# Schematic.net
KiCad netlist of a schematic drawn in Altium Designer
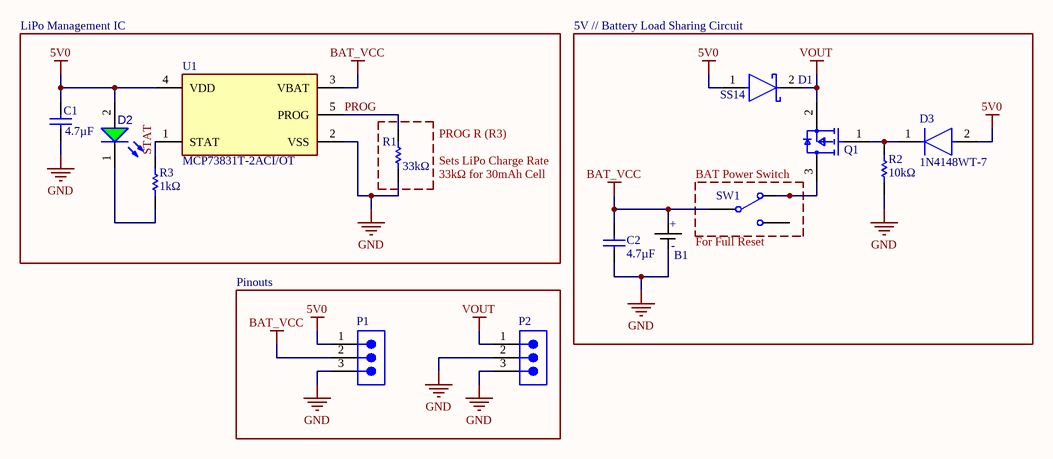
[diagram p0: Schematic.SchDoc]

(export (version "E")
  (design (tool "Eeschema 10.0.6"))
  (components
    (comp (ref "B1") (value "LiPo") (libsource (lib "LiPoSchematicLibrary") (part "3.7V 30mAh LiPo")))
    (comp (ref "C1")
      (value "4.7µF")
      (footprint "CAPC1206(3216)190_L")
      (description "CAP 4.7uF 25V ±5% 1206 (3216 Metric) Thickness 1.9mm SMD")
      (fields (field (name "TOLERANCE") "Â±5%"))
      (libsource (lib "Altium Content Vault") (part "CAP"))
    )
    (comp (ref "C2")
      (value "4.7µF")
      (footprint "CAPC1206(3216)190_L")
      (description "CAP 4.7uF 25V ±5% 1206 (3216 Metric) Thickness 1.9mm SMD")
      (fields (field (name "TOLERANCE") "Â±5%"))
      (libsource (lib "Altium Content Vault") (part "CAP"))
    )
    (comp (ref "D1")
      (value "SS14")
      (footprint "FP-403AE-MFG")
      (description "DIODE SCHOTTKY 40V 1A SMA")
      (fields
        (field (name "MANUFACTURER") "ON Semiconductor")
        (field (name "OCTOPART") "https://octopart.com/ss14-on+semiconductor-29205033")
      )
      (libsource (lib "Altium Content Vault") (part "360ad2f4ac25a952324d13796385471"))
    )
    (comp (ref "D2")
      (value "150120GS75000")
      (footprint "WL-SMCW_1206_150120xx75000")
      (description "WL-SMCW SMT Mono-Color Chip LED Waterclear")
      (libsource (lib "Altium Content Vault") (part "LED_Green_2A-1K"))
    )
    (comp (ref "D3")
      (value "1N4148WT-7")
      (footprint "FP-SOD523-MFG")
      (description "DIODE GEN PURP 80V 125MA SOD523")
      (libsource (lib "Altium Content Vault") (part "d7152d700b627762746794eb795d46e"))
    )
    (comp (ref "P1")
      (value "61300311121")
      (footprint "61300311121")
      (libsource (lib "Altium Content Vault") (part "Header_Male_1R_03P"))
    )
    (comp (ref "P2")
      (value "61300311121")
      (footprint "61300311121")
      (libsource (lib "Altium Content Vault") (part "Header_Male_1R_03P"))
    )
    (comp (ref "Q1")
      (value "IRLML6402TRPBF")
      (footprint "FP-Micro3-MFG")
      (description "MOSFET P-CH 20V 3.7A SOT-23")
      (fields
        (field (name "OCTOPART") "https://octopart.com/irlml6402trpbf-infineon-65874989")
        (field (name "MANUFACTURER") "Infineon")
      )
      (libsource (lib "Altium Content Vault") (part "566027c8dc92b5207d53ac25ab3eb60"))
    )
    (comp (ref "R1")
      (value "33kΩ")
      (footprint "RESC3116X65X40LL10T20")
      (fields (field (name "PART NUMBER") "RC1206JR-1033KL") (field (name "MANUFACTURER") "Yageo"))
      (libsource (lib "Altium Content Vault") (part "RES"))
    )
    (comp (ref "R2")
      (value "10kΩ")
      (footprint "RESC3116X65X40LL10T20")
      (description "Chip Resistor, 10 KOhm, +/- 1%, 0.25 W, -55 to 155 degC, 1206 (3216 Metric), RoHS, Tape and Reel")
      (fields (field (name "TOLERANCE") "1%") (field (name "MANUFACTURER") "Yageo"))
      (libsource (lib "Altium Content Vault") (part "RES-2"))
    )
    (comp (ref "R3")
      (value "1kΩ")
      (footprint "RESC3116X65X40LL10T20")
      (description "Chip Resistor, 1 KOhm, +/- 1%, 0.25 W, -55 to 155 degC, 1206 (3216 Metric), RoHS, Tape and Reel")
      (fields (field (name "TOLERANCE") "1%") (field (name "MANUFACTURER") "Yageo"))
      (libsource (lib "Altium Content Vault") (part "RES-2"))
    )
    (comp (ref "SW1")
      (value "450404015514")
      (footprint "450404015514")
      (description "450404015514 Slide Switch, 0.3A, 5Vdc, Smd Rohs Compliant: Yes")
      (libsource (lib "Altium Content Vault") (part "SPDT"))
    )
    (comp (ref "U1")
      (value "MCP73831T-2ACI/OT")
      (footprint "FP-C04-091-OT-IPC_B")
      (description "IC CONTROLLR LI-ION 4.2V SOT23-5")
      (libsource (lib "Altium Content Vault") (part "61f5a3bb3429d9e0caadea342aa3b19"))
    )
  )
  (nets
    (net (code "1") (name "/PROG") (class "Default")
      (node (ref "R1") (pin "2") (pinfunction "2_2") (pintype "passive"))
      (node (ref "U1") (pin "5") (pinfunction "PROG_5") (pintype "passive"))
    )
    (net (code "2") (name "/STAT") (class "Default")
      (node (ref "R3") (pin "1") (pinfunction "1_1") (pintype "passive"))
      (node (ref "U1") (pin "1") (pinfunction "STAT_1") (pintype "passive"))
    )
    (net (code "3") (name "5V0") (class "Default")
      (node (ref "C1") (pin "2") (pinfunction "2_2") (pintype "passive"))
      (node (ref "D1") (pin "1") (pinfunction "A_1") (pintype "passive"))
      (node (ref "D2") (pin "2") (pinfunction "A_2") (pintype "passive"))
      (node (ref "D3") (pin "2") (pinfunction "A_2") (pintype "passive"))
      (node (ref "P1") (pin "1") (pinfunction "1_1") (pintype "passive"))
      (node (ref "U1") (pin "4") (pinfunction "VDD_4") (pintype "power_in"))
    )
    (net (code "4") (name "BAT_VCC") (class "Default")
      (node (ref "B1") (pin "0") (pinfunction "+_0") (pintype "passive"))
      (node (ref "C2") (pin "2") (pinfunction "2_2") (pintype "passive"))
      (node (ref "P1") (pin "2") (pinfunction "2_2") (pintype "passive"))
      (node (ref "SW1") (pin "COM") (pinfunction "COM_COM") (pintype "passive"))
      (node (ref "U1") (pin "3") (pinfunction "VBAT_3") (pintype "power_in"))
    )
    (net (code "5") (name "GND") (class "Default")
      (node (ref "B1") (pin "1") (pinfunction "-_1") (pintype "passive"))
      (node (ref "C1") (pin "1") (pinfunction "1_1") (pintype "passive"))
      (node (ref "C2") (pin "1") (pinfunction "1_1") (pintype "passive"))
      (node (ref "P1") (pin "3") (pinfunction "3_3") (pintype "passive"))
      (node (ref "P2") (pin "2") (pinfunction "2_2") (pintype "passive"))
      (node (ref "P2") (pin "3") (pinfunction "3_3") (pintype "passive"))
      (node (ref "R1") (pin "1") (pinfunction "1_1") (pintype "passive"))
      (node (ref "R2") (pin "1") (pinfunction "1_1") (pintype "passive"))
      (node (ref "U1") (pin "2") (pinfunction "VSS_2") (pintype "power_in"))
    )
    (net (code "6") (name "Net-(D2-K)") (class "Default")
      (node (ref "D2") (pin "1") (pinfunction "K_1") (pintype "passive"))
      (node (ref "R3") (pin "2") (pinfunction "2_2") (pintype "passive"))
    )
    (net (code "7") (name "Net-(D3-C)") (class "Default")
      (node (ref "D3") (pin "1") (pinfunction "C_1") (pintype "passive"))
      (node (ref "Q1") (pin "1") (pinfunction "G_1") (pintype "passive"))
      (node (ref "R2") (pin "2") (pinfunction "2_2") (pintype "passive"))
    )
    (net (code "8") (name "Net-(Q1-D)") (class "Default")
      (node (ref "Q1") (pin "3") (pinfunction "D_3") (pintype "passive"))
      (node (ref "SW1") (pin "L1") (pinfunction "L1_L1") (pintype "passive"))
    )
    (net (code "9") (name "VOUT") (class "Default")
      (node (ref "D1") (pin "2") (pinfunction "C_2") (pintype "passive"))
      (node (ref "P2") (pin "1") (pinfunction "1_1") (pintype "passive"))
      (node (ref "Q1") (pin "2") (pinfunction "S_2") (pintype "passive"))
    )
    (net (code "10") (name "unconnected-(SW1-PadL2)") (class "Default")
      (node (ref "SW1") (pin "L2") (pinfunction "L2_L2") (pintype "passive"))
    )
  )
)
